# Sheet3.net
KiCad netlist of a schematic drawn in Altium Designer
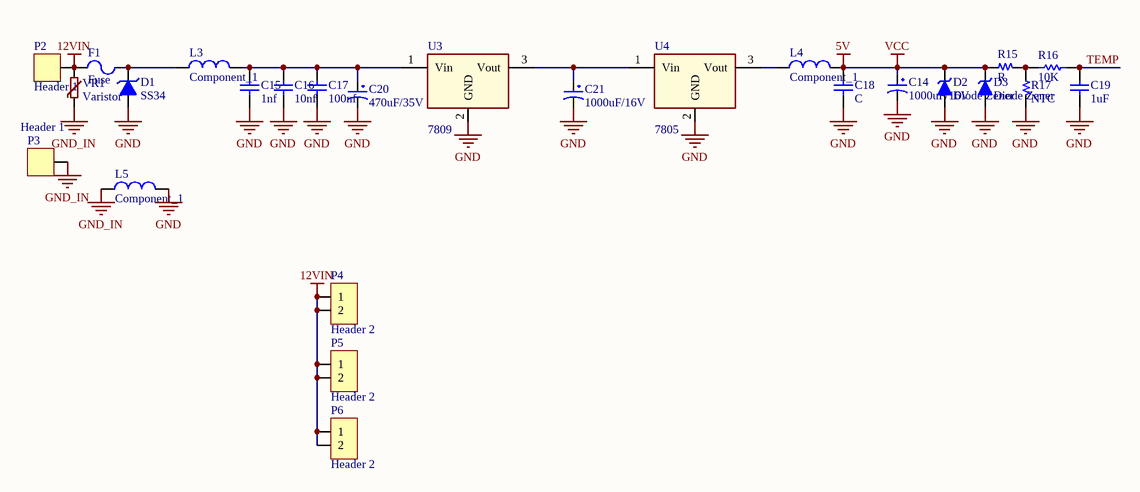
[diagram p0: Sheet3.SchDoc]

(export (version "E")
  (design (tool "Eeschema 10.0.6"))
  (components
    (comp (ref "C14")
      (value "1000uF/16V")
      (footprint "WCAP-PSHP 8x8.7x3.1")
      (description "Cap 1000uF/16V - 220uF/50V")
      (libsource (lib "syhaunguyen") (part "CP4"))
    )
    (comp (ref "C15")
      (value "1nf")
      (footprint "C 0805 (2012)")
      (description "Capacitor non-pol")
      (libsource (lib "BKIT4U_LIB") (part "Capacitor NP"))
    )
    (comp (ref "C16")
      (value "10nf")
      (footprint "C 0805 (2012)")
      (description "Capacitor non-pol")
      (libsource (lib "BKIT4U_LIB") (part "Capacitor NP"))
    )
    (comp (ref "C17")
      (value "100nf")
      (footprint "C 0805 (2012)")
      (description "Capacitor non-pol")
      (libsource (lib "BKIT4U_LIB") (part "Capacitor NP"))
    )
    (comp (ref "C18")
      (value "C")
      (footprint "C 0805 (2012)")
      (description "Capacitor non-pol")
      (libsource (lib "BKIT4U_LIB") (part "Capacitor NP"))
    )
    (comp (ref "C19")
      (value "1uF")
      (footprint "C 0805 (2012)")
      (description "Capacitor non-pol")
      (libsource (lib "BKIT4U_LIB") (part "Capacitor NP"))
    )
    (comp (ref "C20")
      (value "470uF/35V")
      (footprint "WCAP-PSHP 8x8.7x3.1")
      (description "Cap 100uF/35V - 470uF/16V")
      (libsource (lib "syhaunguyen") (part "CP3"))
    )
    (comp (ref "C21")
      (value "1000uF/16V")
      (footprint "WCAP-PSHP 8x8.7x3.1")
      (description "Cap 1000uF/16V - 220uF/50V")
      (libsource (lib "syhaunguyen") (part "CP4"))
    )
    (comp (ref "D1")
      (value "SS34")
      (footprint "DO-214AC (SMA)")
      (libsource (lib "syhaunguyen") (part "Zener"))
    )
    (comp (ref "D2")
      (value "Diode Zener")
      (footprint "SOD-80")
      (description "Zener Diode")
      (fields (field (name "PUBLISHER") "Altium Limited"))
      (libsource (lib "BKIT4U_LIB") (part "Diode Zener"))
    )
    (comp (ref "D3")
      (value "Diode Zener")
      (footprint "SOD-80")
      (description "Zener Diode")
      (fields (field (name "PUBLISHER") "Altium Limited"))
      (libsource (lib "BKIT4U_LIB") (part "Diode Zener"))
    )
    (comp (ref "F1")
      (value "Fuse")
      (footprint "DCAR Fuse holder")
      (libsource (lib "chipfc_altium_libs") (part "Fuse"))
    )
    (comp (ref "L3")
      (value "Component_1")
      (footprint "1210")
      (libsource (lib "Integrated_Library1") (part "Component_1"))
    )
    (comp (ref "L4")
      (value "Component_1")
      (footprint "Inductor SMD 4.8x4.8")
      (libsource (lib "Integrated_Library1") (part "Component_1"))
    )
    (comp (ref "L5")
      (value "Component_1")
      (footprint "1210")
      (libsource (lib "Integrated_Library1") (part "Component_1"))
    )
    (comp (ref "P2")
      (value "Header 1")
      (footprint "HDR/Terminal/1/copper/8.8")
      (description "Header, 1-Pin")
      (libsource (lib "chipfc_altium_libs") (part "Header 1"))
    )
    (comp (ref "P3")
      (value "Header 1")
      (footprint "HDR/Terminal/1/copper/8.8")
      (description "Header, 1-Pin")
      (libsource (lib "chipfc_altium_libs") (part "Header 1"))
    )
    (comp (ref "P4")
      (value "Header 2")
      (footprint "HDR Domino 2")
      (description "Header, 2-Pin")
      (fields (field (name "PUBLISHER") "Altium Limited"))
      (libsource (lib "BKIT4U_LIB") (part "Header 2"))
    )
    (comp (ref "P5")
      (value "Header 2")
      (footprint "HDR Domino 2")
      (description "Header, 2-Pin")
      (fields (field (name "PUBLISHER") "Altium Limited"))
      (libsource (lib "BKIT4U_LIB") (part "Header 2"))
    )
    (comp (ref "P6")
      (value "Header 2")
      (footprint "HDR Domino 2")
      (description "Header, 2-Pin")
      (fields (field (name "PUBLISHER") "Altium Limited"))
      (libsource (lib "BKIT4U_LIB") (part "Header 2"))
    )
    (comp (ref "R15")
      (value "R")
      (footprint "R 0805")
      (description "Resistor")
      (libsource (lib "chipfc_altium_libs") (part "Resistor"))
    )
    (comp (ref "R16")
      (value "10K")
      (footprint "R 0805 (2012)")
      (description "Resistor")
      (fields (field (name "PUBLISHER") "Altium Limited"))
      (libsource (lib "BKIT4U_LIB") (part "Resistor"))
    )
    (comp (ref "R17")
      (value "NTC")
      (footprint "R 1/4W/300")
      (description "Resistor")
      (libsource (lib "chipfc_altium_libs") (part "Resistor"))
    )
    (comp (ref "U3")
      (value "7809")
      (footprint "TO-252 (DPAK)")
      (description "LDO Fixed Voltage regulator")
      (libsource (lib "BKIT4U_LIB") (part "78xx"))
    )
    (comp (ref "U4")
      (value "7805")
      (footprint "TO-252 (DPAK)")
      (description "LDO Fixed Voltage regulator")
      (libsource (lib "BKIT4U_LIB") (part "78xx"))
    )
    (comp (ref "VR1")
      (value "Varistor")
      (footprint "VARISTOR DISC 5MM/7MM")
      (libsource (lib "chipfc_altium_libs") (part "Varistor"))
    )
  )
  (nets
    (net (code "1") (name "/TEMP") (class "Default")
      (node (ref "C19") (pin "1") (pinfunction "1_1") (pintype "passive"))
      (node (ref "R16") (pin "2") (pinfunction "2_2") (pintype "passive"))
    )
    (net (code "2") (name "5V") (class "Default")
      (node (ref "C14") (pin "1") (pinfunction "1_1") (pintype "passive"))
      (node (ref "C18") (pin "1") (pinfunction "1_1") (pintype "passive"))
      (node (ref "D2") (pin "2") (pinfunction "K_2") (pintype "passive"))
      (node (ref "D3") (pin "2") (pinfunction "K_2") (pintype "passive"))
      (node (ref "L4") (pin "2") (pinfunction "2_2") (pintype "passive"))
      (node (ref "R15") (pin "1") (pinfunction "1_1") (pintype "passive"))
    )
    (net (code "3") (name "12VIN") (class "Default")
      (node (ref "F1") (pin "1") (pinfunction "1_1") (pintype "passive"))
      (node (ref "P2") (pin "1") (pinfunction "1_1") (pintype "passive"))
      (node (ref "P4") (pin "1") (pinfunction "1_1") (pintype "passive"))
      (node (ref "P4") (pin "2") (pinfunction "2_2") (pintype "passive"))
      (node (ref "P5") (pin "1") (pinfunction "1_1") (pintype "passive"))
      (node (ref "P5") (pin "2") (pinfunction "2_2") (pintype "passive"))
      (node (ref "P6") (pin "1") (pinfunction "1_1") (pintype "passive"))
      (node (ref "P6") (pin "2") (pinfunction "2_2") (pintype "passive"))
      (node (ref "VR1") (pin "1") (pinfunction "1_1") (pintype "passive"))
    )
    (net (code "4") (name "GND") (class "Default")
      (node (ref "C14") (pin "2") (pinfunction "2_2") (pintype "passive"))
      (node (ref "C15") (pin "2") (pinfunction "2_2") (pintype "passive"))
      (node (ref "C16") (pin "2") (pinfunction "2_2") (pintype "passive"))
      (node (ref "C17") (pin "2") (pinfunction "2_2") (pintype "passive"))
      (node (ref "C18") (pin "2") (pinfunction "2_2") (pintype "passive"))
      (node (ref "C19") (pin "2") (pinfunction "2_2") (pintype "passive"))
      (node (ref "C20") (pin "2") (pinfunction "2_2") (pintype "passive"))
      (node (ref "C21") (pin "2") (pinfunction "2_2") (pintype "passive"))
      (node (ref "D1") (pin "1") (pinfunction "A_1") (pintype "passive"))
      (node (ref "D2") (pin "1") (pinfunction "A_1") (pintype "passive"))
      (node (ref "D3") (pin "1") (pinfunction "A_1") (pintype "passive"))
      (node (ref "L5") (pin "2") (pinfunction "2_2") (pintype "passive"))
      (node (ref "R17") (pin "2") (pinfunction "2_2") (pintype "passive"))
      (node (ref "U3") (pin "2") (pinfunction "GND_2") (pintype "passive"))
      (node (ref "U4") (pin "2") (pinfunction "GND_2") (pintype "passive"))
    )
    (net (code "5") (name "GND_IN") (class "Default")
      (node (ref "L5") (pin "1") (pinfunction "1_1") (pintype "passive"))
      (node (ref "P3") (pin "1") (pinfunction "1_1") (pintype "passive"))
      (node (ref "VR1") (pin "2") (pinfunction "2_2") (pintype "passive"))
    )
    (net (code "6") (name "Net-(D1-K)") (class "Default")
      (node (ref "D1") (pin "2") (pinfunction "K_2") (pintype "passive"))
      (node (ref "F1") (pin "2") (pinfunction "2_2") (pintype "passive"))
      (node (ref "L3") (pin "1") (pinfunction "1_1") (pintype "passive"))
    )
    (net (code "7") (name "Net-(R15-Pad2)") (class "Default")
      (node (ref "R15") (pin "2") (pinfunction "2_2") (pintype "passive"))
      (node (ref "R16") (pin "1") (pinfunction "1_1") (pintype "passive"))
      (node (ref "R17") (pin "1") (pinfunction "1_1") (pintype "passive"))
    )
    (net (code "8") (name "Net-(U3-Vin)") (class "Default")
      (node (ref "C15") (pin "1") (pinfunction "1_1") (pintype "passive"))
      (node (ref "C16") (pin "1") (pinfunction "1_1") (pintype "passive"))
      (node (ref "C17") (pin "1") (pinfunction "1_1") (pintype "passive"))
      (node (ref "C20") (pin "1") (pinfunction "1_1") (pintype "passive"))
      (node (ref "L3") (pin "2") (pinfunction "2_2") (pintype "passive"))
      (node (ref "U3") (pin "1") (pinfunction "Vin_1") (pintype "power_in"))
    )
    (net (code "9") (name "Net-(U3-Vout)") (class "Default")
      (node (ref "C21") (pin "1") (pinfunction "1_1") (pintype "passive"))
      (node (ref "U3") (pin "3") (pinfunction "Vout_3") (pintype "passive"))
      (node (ref "U4") (pin "1") (pinfunction "Vin_1") (pintype "power_in"))
    )
    (net (code "10") (name "Net-(U4-Vout)") (class "Default")
      (node (ref "L4") (pin "1") (pinfunction "1_1") (pintype "passive"))
      (node (ref "U4") (pin "3") (pinfunction "Vout_3") (pintype "passive"))
    )
  )
)
